# PowCarbinBoard_Sensor.net
KiCad netlist of a schematic drawn in Altium Designer
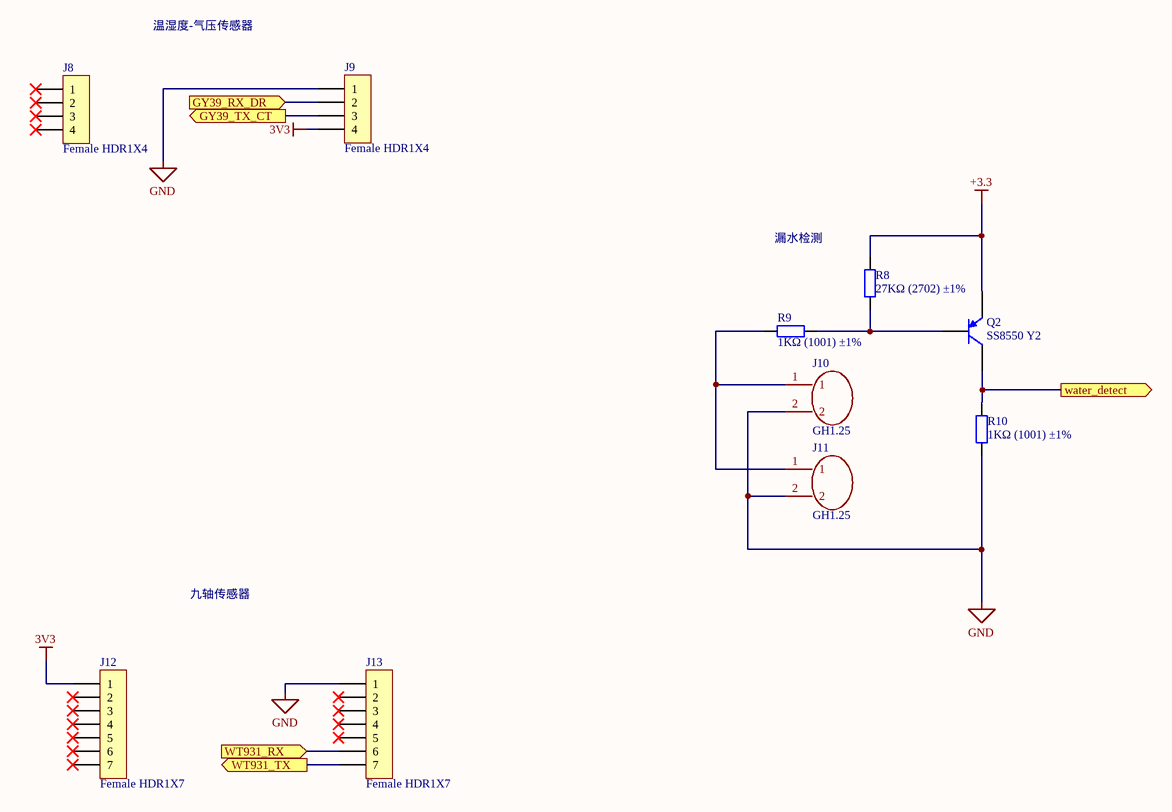
[diagram p0: PowCarbinBoard_Sensor.SchDoc]

(export (version "E")
  (design (tool "Eeschema 10.0.6"))
  (components
    (comp (ref "J8")
      (value "Female HDR1X4")
      (footprint "Fe-HDR1X4/2.54-S")
      (libsource (lib "排母") (part "Female HDR1X4"))
    )
    (comp (ref "J9")
      (value "Female HDR1X4")
      (footprint "Fe-HDR1X4/2.54-S")
      (libsource (lib "排母") (part "Female HDR1X4"))
    )
    (comp (ref "J10")
      (value "GH1.25")
      (footprint "GH1.25 2pin")
      (libsource (lib "MySchLib") (part "GH1.25 2pin"))
    )
    (comp (ref "J11")
      (value "GH1.25")
      (footprint "GH1.25 2pin")
      (libsource (lib "MySchLib") (part "GH1.25 2pin"))
    )
    (comp (ref "J12")
      (value "Female HDR1X7")
      (footprint "Fe-HDR1X7/2.54-S")
      (libsource (lib "排母") (part "Female HDR1X7"))
    )
    (comp (ref "J13")
      (value "Female HDR1X7")
      (footprint "Fe-HDR1X7/2.54-S")
      (libsource (lib "排母") (part "Female HDR1X7"))
    )
    (comp (ref "Q2")
      (value "SS8550 Y2")
      (footprint "SOT-23(SOT-23-3)")
      (description "三极管")
      (libsource (lib "Miscellaneous Devices LC") (part "SOT-23 SS8550 Y2"))
    )
    (comp (ref "R8")
      (value "27KΩ (2702) ±1%")
      (footprint "0603_R")
      (description "贴片电阻")
      (libsource (lib "Miscellaneous Devices LC") (part "0603 27KΩ (2702) 1%"))
    )
    (comp (ref "R9")
      (value "1KΩ (1001) ±1%")
      (footprint "0603_R")
      (description "贴片电阻")
      (libsource (lib "") (part "0603 1KΩ (1001) 1%_1"))
    )
    (comp (ref "R10")
      (value "1KΩ (1001) ±1%")
      (footprint "0603_R")
      (description "贴片电阻")
      (libsource (lib "Miscellaneous Devices LC") (part "0603 1KΩ (1001) 1%"))
    )
  )
  (nets
    (net (code "1") (name "+3.3") (class "Default")
      (node (ref "Q2") (pin "2") (pinfunction "E_2") (pintype "passive"))
      (node (ref "R8") (pin "2") (pinfunction "2_2") (pintype "passive"))
    )
    (net (code "2") (name "/GY39_RX_DR") (class "Default")
      (node (ref "J9") (pin "2") (pinfunction "2_2") (pintype "passive"))
    )
    (net (code "3") (name "/GY39_TX_CT") (class "Default")
      (node (ref "J9") (pin "3") (pinfunction "3_3") (pintype "passive"))
    )
    (net (code "4") (name "/WT931_RX") (class "Default")
      (node (ref "J13") (pin "6") (pinfunction "6_6") (pintype "passive"))
    )
    (net (code "5") (name "/WT931_TX") (class "Default")
      (node (ref "J13") (pin "7") (pinfunction "7_7") (pintype "passive"))
    )
    (net (code "6") (name "/water_detect") (class "Default")
      (node (ref "Q2") (pin "3") (pinfunction "C_3") (pintype "passive"))
      (node (ref "R10") (pin "2") (pinfunction "2_2") (pintype "passive"))
    )
    (net (code "7") (name "3V3") (class "Default")
      (node (ref "J12") (pin "1") (pinfunction "1_1") (pintype "passive"))
      (node (ref "J9") (pin "4") (pinfunction "4_4") (pintype "passive"))
    )
    (net (code "8") (name "GND") (class "Default")
      (node (ref "J10") (pin "2") (pinfunction "2_2") (pintype "passive"))
      (node (ref "J11") (pin "2") (pinfunction "2_2") (pintype "passive"))
      (node (ref "J13") (pin "1") (pinfunction "1_1") (pintype "passive"))
      (node (ref "J9") (pin "1") (pinfunction "1_1") (pintype "passive"))
      (node (ref "R10") (pin "1") (pinfunction "1_1") (pintype "passive"))
    )
    (net (code "9") (name "Net-(J10-Pad1)") (class "Default")
      (node (ref "J10") (pin "1") (pinfunction "1_1") (pintype "passive"))
      (node (ref "J11") (pin "1") (pinfunction "1_1") (pintype "passive"))
      (node (ref "R9") (pin "1") (pinfunction "1_1") (pintype "passive"))
    )
    (net (code "10") (name "Net-(Q2-B)") (class "Default")
      (node (ref "Q2") (pin "1") (pinfunction "B_1") (pintype "passive"))
      (node (ref "R8") (pin "1") (pinfunction "1_1") (pintype "passive"))
      (node (ref "R9") (pin "2") (pinfunction "2_2") (pintype "passive"))
    )
    (net (code "11") (name "unconnected-(J8-Pad1)") (class "Default")
      (node (ref "J8") (pin "1") (pinfunction "1_1") (pintype "passive+no_connect"))
    )
    (net (code "12") (name "unconnected-(J8-Pad2)") (class "Default")
      (node (ref "J8") (pin "2") (pinfunction "2_2") (pintype "passive+no_connect"))
    )
    (net (code "13") (name "unconnected-(J8-Pad3)") (class "Default")
      (node (ref "J8") (pin "3") (pinfunction "3_3") (pintype "passive+no_connect"))
    )
    (net (code "14") (name "unconnected-(J8-Pad4)") (class "Default")
      (node (ref "J8") (pin "4") (pinfunction "4_4") (pintype "passive+no_connect"))
    )
    (net (code "15") (name "unconnected-(J12-Pad2)") (class "Default")
      (node (ref "J12") (pin "2") (pinfunction "2_2") (pintype "passive+no_connect"))
    )
    (net (code "16") (name "unconnected-(J12-Pad3)") (class "Default")
      (node (ref "J12") (pin "3") (pinfunction "3_3") (pintype "passive+no_connect"))
    )
    (net (code "17") (name "unconnected-(J12-Pad4)") (class "Default")
      (node (ref "J12") (pin "4") (pinfunction "4_4") (pintype "passive+no_connect"))
    )
    (net (code "18") (name "unconnected-(J12-Pad5)") (class "Default")
      (node (ref "J12") (pin "5") (pinfunction "5_5") (pintype "passive+no_connect"))
    )
    (net (code "19") (name "unconnected-(J12-Pad6)") (class "Default")
      (node (ref "J12") (pin "6") (pinfunction "6_6") (pintype "passive+no_connect"))
    )
    (net (code "20") (name "unconnected-(J12-Pad7)") (class "Default")
      (node (ref "J12") (pin "7") (pinfunction "7_7") (pintype "passive+no_connect"))
    )
    (net (code "21") (name "unconnected-(J13-Pad2)") (class "Default")
      (node (ref "J13") (pin "2") (pinfunction "2_2") (pintype "passive+no_connect"))
    )
    (net (code "22") (name "unconnected-(J13-Pad3)") (class "Default")
      (node (ref "J13") (pin "3") (pinfunction "3_3") (pintype "passive+no_connect"))
    )
    (net (code "23") (name "unconnected-(J13-Pad4)") (class "Default")
      (node (ref "J13") (pin "4") (pinfunction "4_4") (pintype "passive+no_connect"))
    )
    (net (code "24") (name "unconnected-(J13-Pad5)") (class "Default")
      (node (ref "J13") (pin "5") (pinfunction "5_5") (pintype "passive+no_connect"))
    )
  )
)
